# Arduino_Car_Sheet.net
KiCad netlist of a schematic drawn in Altium Designer
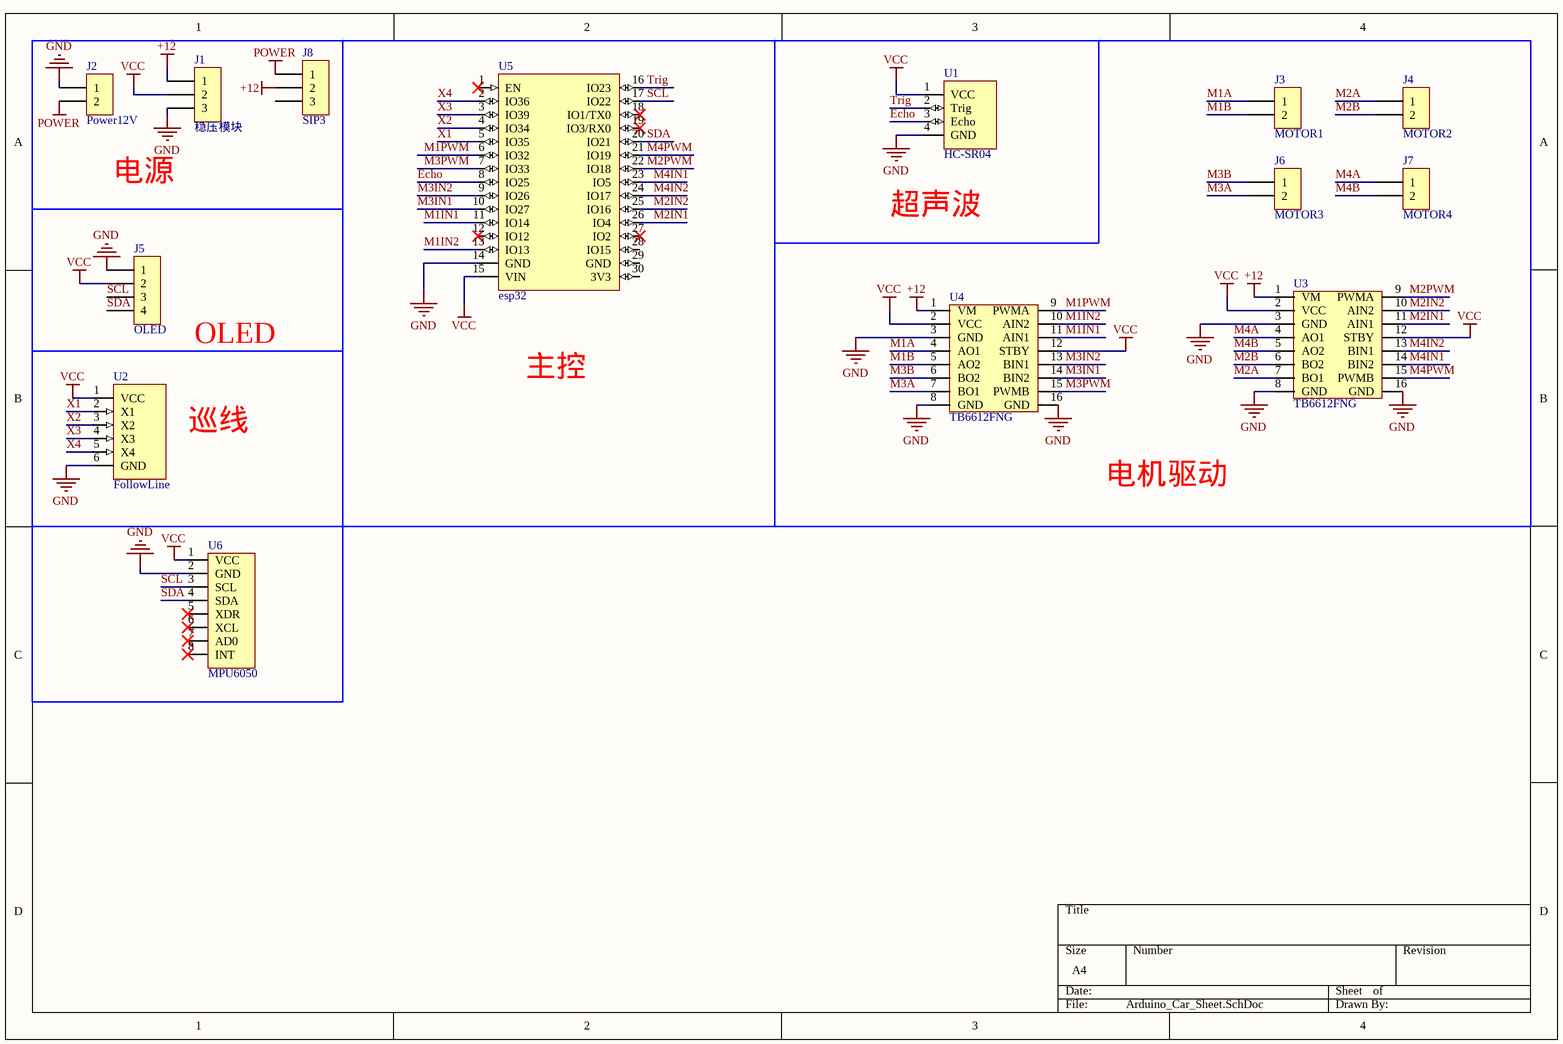
[diagram p0: Arduino_Car_Sheet.SchDoc]

(export (version "E")
  (design (tool "Eeschema 10.0.6"))
  (components
    (comp (ref "J1")
      (value "稳压模块")
      (footprint "SIP3")
      (description "jointbar")
      (libsource (lib "YTschlib") (part "SIP3"))
    )
    (comp (ref "J2")
      (value "Power12V")
      (footprint "XH2.54-WS-2P")
      (description "jointbar")
      (libsource (lib "YTschlib") (part "SIP2"))
    )
    (comp (ref "J3")
      (value "MOTOR1")
      (footprint "XH2.54-WS-2P")
      (description "jointbar")
      (libsource (lib "YTschlib") (part "SIP2"))
    )
    (comp (ref "J4")
      (value "MOTOR2")
      (footprint "XH2.54-WS-2P")
      (description "jointbar")
      (libsource (lib "YTschlib") (part "SIP2"))
    )
    (comp (ref "J5")
      (value "OLED")
      (footprint "SIP_4P-P2.54-V-F")
      (description "jointbar")
      (libsource (lib "YTschlib") (part "SIP4"))
    )
    (comp (ref "J6")
      (value "MOTOR3")
      (footprint "XH2.54-WS-2P")
      (description "jointbar")
      (libsource (lib "YTschlib") (part "SIP2"))
    )
    (comp (ref "J7")
      (value "MOTOR4")
      (footprint "XH2.54-WS-2P")
      (description "jointbar")
      (libsource (lib "YTschlib") (part "SIP2"))
    )
    (comp (ref "J8")
      (value "SIP3")
      (footprint "SS-12D10")
      (description "jointbar")
      (libsource (lib "YTschlib") (part "SIP3"))
    )
    (comp (ref "U1")
      (value "HC-SR04")
      (footprint "SIP_4P-P2.54-V-F")
      (libsource (lib "YTschlib") (part "HC-SR04"))
    )
    (comp (ref "U2")
      (value "FollowLine")
      (footprint "XH2.54-WS-6P")
      (libsource (lib "YTschlib") (part "FollowLine"))
    )
    (comp (ref "U3")
      (value "TB6612FNG")
      (footprint "TB6612FNG")
      (libsource (lib "YTschlib") (part "TB6612FNG"))
    )
    (comp (ref "U4")
      (value "TB6612FNG")
      (footprint "TB6612FNG")
      (libsource (lib "YTschlib") (part "TB6612FNG"))
    )
    (comp (ref "U5")
      (value "esp32")
      (footprint "ESP32")
      (libsource (lib "YTschlib") (part "ESP32NodeMcu-32S"))
    )
    (comp (ref "U6") (value "MPU6050") (footprint "SIP8") (libsource (lib "YTschlib") (part "MPU6050")))
  )
  (nets
    (net (code "1") (name "+12") (class "Default")
      (node (ref "J1") (pin "1") (pinfunction "1_1") (pintype "passive"))
      (node (ref "J8") (pin "2") (pinfunction "2_2") (pintype "passive"))
      (node (ref "U3") (pin "1") (pinfunction "VM_1") (pintype "passive"))
      (node (ref "U4") (pin "1") (pinfunction "VM_1") (pintype "passive"))
    )
    (net (code "2") (name "/Echo") (class "Default")
      (node (ref "U1") (pin "3") (pinfunction "Echo_3") (pintype "bidirectional"))
      (node (ref "U5") (pin "8") (pinfunction "IO25_8") (pintype "bidirectional"))
    )
    (net (code "3") (name "/M1A") (class "Default")
      (node (ref "J3") (pin "1") (pinfunction "1_1") (pintype "passive"))
      (node (ref "U4") (pin "4") (pinfunction "AO1_4") (pintype "passive"))
    )
    (net (code "4") (name "/M1B") (class "Default")
      (node (ref "J3") (pin "2") (pinfunction "2_2") (pintype "passive"))
      (node (ref "U4") (pin "5") (pinfunction "AO2_5") (pintype "passive"))
    )
    (net (code "5") (name "/M1IN1") (class "Default")
      (node (ref "U4") (pin "11") (pinfunction "AIN1_11") (pintype "passive"))
      (node (ref "U5") (pin "11") (pinfunction "IO14_11") (pintype "bidirectional"))
    )
    (net (code "6") (name "/M1IN2") (class "Default")
      (node (ref "U4") (pin "10") (pinfunction "AIN2_10") (pintype "passive"))
      (node (ref "U5") (pin "13") (pinfunction "IO13_13") (pintype "bidirectional"))
    )
    (net (code "7") (name "/M1PWM") (class "Default")
      (node (ref "U4") (pin "9") (pinfunction "PWMA_9") (pintype "passive"))
      (node (ref "U5") (pin "6") (pinfunction "IO32_6") (pintype "bidirectional"))
    )
    (net (code "8") (name "/M2A") (class "Default")
      (node (ref "J4") (pin "1") (pinfunction "1_1") (pintype "passive"))
      (node (ref "U3") (pin "7") (pinfunction "BO1_7") (pintype "passive"))
    )
    (net (code "9") (name "/M2B") (class "Default")
      (node (ref "J4") (pin "2") (pinfunction "2_2") (pintype "passive"))
      (node (ref "U3") (pin "6") (pinfunction "BO2_6") (pintype "passive"))
    )
    (net (code "10") (name "/M2IN1") (class "Default")
      (node (ref "U3") (pin "11") (pinfunction "AIN1_11") (pintype "passive"))
      (node (ref "U5") (pin "26") (pinfunction "IO4_26") (pintype "bidirectional"))
    )
    (net (code "11") (name "/M2IN2") (class "Default")
      (node (ref "U3") (pin "10") (pinfunction "AIN2_10") (pintype "passive"))
      (node (ref "U5") (pin "25") (pinfunction "IO16_25") (pintype "bidirectional"))
    )
    (net (code "12") (name "/M2PWM") (class "Default")
      (node (ref "U3") (pin "9") (pinfunction "PWMA_9") (pintype "passive"))
      (node (ref "U5") (pin "22") (pinfunction "IO18_22") (pintype "bidirectional"))
    )
    (net (code "13") (name "/M3A") (class "Default")
      (node (ref "J6") (pin "2") (pinfunction "2_2") (pintype "passive"))
      (node (ref "U4") (pin "7") (pinfunction "BO1_7") (pintype "passive"))
    )
    (net (code "14") (name "/M3B") (class "Default")
      (node (ref "J6") (pin "1") (pinfunction "1_1") (pintype "passive"))
      (node (ref "U4") (pin "6") (pinfunction "BO2_6") (pintype "passive"))
    )
    (net (code "15") (name "/M3IN1") (class "Default")
      (node (ref "U4") (pin "14") (pinfunction "BIN2_14") (pintype "passive"))
      (node (ref "U5") (pin "10") (pinfunction "IO27_10") (pintype "bidirectional"))
    )
    (net (code "16") (name "/M3IN2") (class "Default")
      (node (ref "U4") (pin "13") (pinfunction "BIN1_13") (pintype "passive"))
      (node (ref "U5") (pin "9") (pinfunction "IO26_9") (pintype "bidirectional"))
    )
    (net (code "17") (name "/M3PWM") (class "Default")
      (node (ref "U4") (pin "15") (pinfunction "PWMB_15") (pintype "passive"))
      (node (ref "U5") (pin "7") (pinfunction "IO33_7") (pintype "bidirectional"))
    )
    (net (code "18") (name "/M4A") (class "Default")
      (node (ref "J7") (pin "1") (pinfunction "1_1") (pintype "passive"))
      (node (ref "U3") (pin "4") (pinfunction "AO1_4") (pintype "passive"))
    )
    (net (code "19") (name "/M4B") (class "Default")
      (node (ref "J7") (pin "2") (pinfunction "2_2") (pintype "passive"))
      (node (ref "U3") (pin "5") (pinfunction "AO2_5") (pintype "passive"))
    )
    (net (code "20") (name "/M4IN1") (class "Default")
      (node (ref "U3") (pin "14") (pinfunction "BIN2_14") (pintype "passive"))
      (node (ref "U5") (pin "23") (pinfunction "IO5_23") (pintype "bidirectional"))
    )
    (net (code "21") (name "/M4IN2") (class "Default")
      (node (ref "U3") (pin "13") (pinfunction "BIN1_13") (pintype "passive"))
      (node (ref "U5") (pin "24") (pinfunction "IO17_24") (pintype "bidirectional"))
    )
    (net (code "22") (name "/M4PWM") (class "Default")
      (node (ref "U3") (pin "15") (pinfunction "PWMB_15") (pintype "passive"))
      (node (ref "U5") (pin "21") (pinfunction "IO19_21") (pintype "bidirectional"))
    )
    (net (code "23") (name "/SCL") (class "Default")
      (node (ref "J5") (pin "3") (pinfunction "3_3") (pintype "passive"))
      (node (ref "U5") (pin "17") (pinfunction "IO22_17") (pintype "bidirectional"))
      (node (ref "U6") (pin "3") (pinfunction "SCL_3") (pintype "passive"))
    )
    (net (code "24") (name "/SDA") (class "Default")
      (node (ref "J5") (pin "4") (pinfunction "4_4") (pintype "passive"))
      (node (ref "U5") (pin "20") (pinfunction "IO21_20") (pintype "bidirectional"))
      (node (ref "U6") (pin "4") (pinfunction "SDA_4") (pintype "passive"))
    )
    (net (code "25") (name "/Trig") (class "Default")
      (node (ref "U1") (pin "2") (pinfunction "Trig_2") (pintype "bidirectional"))
      (node (ref "U5") (pin "16") (pinfunction "IO23_16") (pintype "bidirectional"))
    )
    (net (code "26") (name "/X1") (class "Default")
      (node (ref "U2") (pin "2") (pinfunction "X1_2") (pintype "input"))
      (node (ref "U5") (pin "5") (pinfunction "IO35_5") (pintype "bidirectional"))
    )
    (net (code "27") (name "/X2") (class "Default")
      (node (ref "U2") (pin "3") (pinfunction "X2_3") (pintype "input"))
      (node (ref "U5") (pin "4") (pinfunction "IO34_4") (pintype "bidirectional"))
    )
    (net (code "28") (name "/X3") (class "Default")
      (node (ref "U2") (pin "4") (pinfunction "X3_4") (pintype "input"))
      (node (ref "U5") (pin "3") (pinfunction "IO39_3") (pintype "bidirectional"))
    )
    (net (code "29") (name "/X4") (class "Default")
      (node (ref "U2") (pin "5") (pinfunction "X4_5") (pintype "input"))
      (node (ref "U5") (pin "2") (pinfunction "IO36_2") (pintype "bidirectional"))
    )
    (net (code "30") (name "GND") (class "Default")
      (node (ref "J1") (pin "3") (pinfunction "3_3") (pintype "passive"))
      (node (ref "J2") (pin "1") (pinfunction "1_1") (pintype "passive"))
      (node (ref "J5") (pin "1") (pinfunction "1_1") (pintype "passive"))
      (node (ref "U1") (pin "4") (pinfunction "GND_4") (pintype "power_in"))
      (node (ref "U2") (pin "6") (pinfunction "GND_6") (pintype "power_in"))
      (node (ref "U3") (pin "16") (pinfunction "GND_16") (pintype "passive"))
      (node (ref "U3") (pin "3") (pinfunction "GND_3") (pintype "passive"))
      (node (ref "U3") (pin "8") (pinfunction "GND_8") (pintype "passive"))
      (node (ref "U4") (pin "16") (pinfunction "GND_16") (pintype "passive"))
      (node (ref "U4") (pin "3") (pinfunction "GND_3") (pintype "passive"))
      (node (ref "U4") (pin "8") (pinfunction "GND_8") (pintype "passive"))
      (node (ref "U5") (pin "14") (pinfunction "GND_14") (pintype "power_in"))
      (node (ref "U6") (pin "2") (pinfunction "GND_2") (pintype "passive"))
    )
    (net (code "31") (name "POWER") (class "Default")
      (node (ref "J2") (pin "2") (pinfunction "2_2") (pintype "passive"))
      (node (ref "J8") (pin "1") (pinfunction "1_1") (pintype "passive"))
    )
    (net (code "32") (name "VCC") (class "Default")
      (node (ref "J1") (pin "2") (pinfunction "2_2") (pintype "passive"))
      (node (ref "J5") (pin "2") (pinfunction "2_2") (pintype "passive"))
      (node (ref "U1") (pin "1") (pinfunction "VCC_1") (pintype "power_in"))
      (node (ref "U2") (pin "1") (pinfunction "VCC_1") (pintype "power_in"))
      (node (ref "U3") (pin "12") (pinfunction "STBY_12") (pintype "passive"))
      (node (ref "U3") (pin "2") (pinfunction "VCC_2") (pintype "passive"))
      (node (ref "U4") (pin "12") (pinfunction "STBY_12") (pintype "passive"))
      (node (ref "U4") (pin "2") (pinfunction "VCC_2") (pintype "passive"))
      (node (ref "U5") (pin "15") (pinfunction "VIN_15") (pintype "power_in"))
      (node (ref "U6") (pin "1") (pinfunction "VCC_1") (pintype "passive"))
    )
    (net (code "33") (name "unconnected-(J8-Pad3)") (class "Default")
      (node (ref "J8") (pin "3") (pinfunction "3_3") (pintype "passive"))
    )
    (net (code "34") (name "unconnected-(U5-3V3-Pad30)") (class "Default")
      (node (ref "U5") (pin "30") (pinfunction "3V3_30") (pintype "bidirectional"))
    )
    (net (code "35") (name "unconnected-(U5-EN-Pad1)") (class "Default")
      (node (ref "U5") (pin "1") (pinfunction "EN_1") (pintype "input+no_connect"))
    )
    (net (code "36") (name "unconnected-(U5-GND-Pad29)") (class "Default")
      (node (ref "U5") (pin "29") (pinfunction "GND_29") (pintype "bidirectional"))
    )
    (net (code "37") (name "unconnected-(U5-IO1{slash}TX0-Pad18)") (class "Default")
      (node (ref "U5") (pin "18") (pinfunction "IO1/TX0_18") (pintype "bidirectional+no_connect"))
    )
    (net (code "38") (name "unconnected-(U5-IO2-Pad27)") (class "Default")
      (node (ref "U5") (pin "27") (pinfunction "IO2_27") (pintype "bidirectional+no_connect"))
    )
    (net (code "39") (name "unconnected-(U5-IO3{slash}RX0-Pad19)") (class "Default")
      (node (ref "U5") (pin "19") (pinfunction "IO3/RX0_19") (pintype "bidirectional+no_connect"))
    )
    (net (code "40") (name "unconnected-(U5-IO12-Pad12)") (class "Default")
      (node (ref "U5") (pin "12") (pinfunction "IO12_12") (pintype "bidirectional+no_connect"))
    )
    (net (code "41") (name "unconnected-(U5-IO15-Pad28)") (class "Default")
      (node (ref "U5") (pin "28") (pinfunction "IO15_28") (pintype "bidirectional"))
    )
    (net (code "42") (name "unconnected-(U6-AD0-Pad7)") (class "Default")
      (node (ref "U6") (pin "7") (pinfunction "AD0_7") (pintype "passive+no_connect"))
    )
    (net (code "43") (name "unconnected-(U6-INT-Pad8)") (class "Default")
      (node (ref "U6") (pin "8") (pinfunction "INT_8") (pintype "passive+no_connect"))
    )
    (net (code "44") (name "unconnected-(U6-XCL-Pad6)") (class "Default")
      (node (ref "U6") (pin "6") (pinfunction "XCL_6") (pintype "passive+no_connect"))
    )
    (net (code "45") (name "unconnected-(U6-XDR-Pad5)") (class "Default")
      (node (ref "U6") (pin "5") (pinfunction "XDR_5") (pintype "passive+no_connect"))
    )
  )
)
